# Bluetooth_Module_1R0.net
KiCad netlist of a schematic drawn in Altium Designer
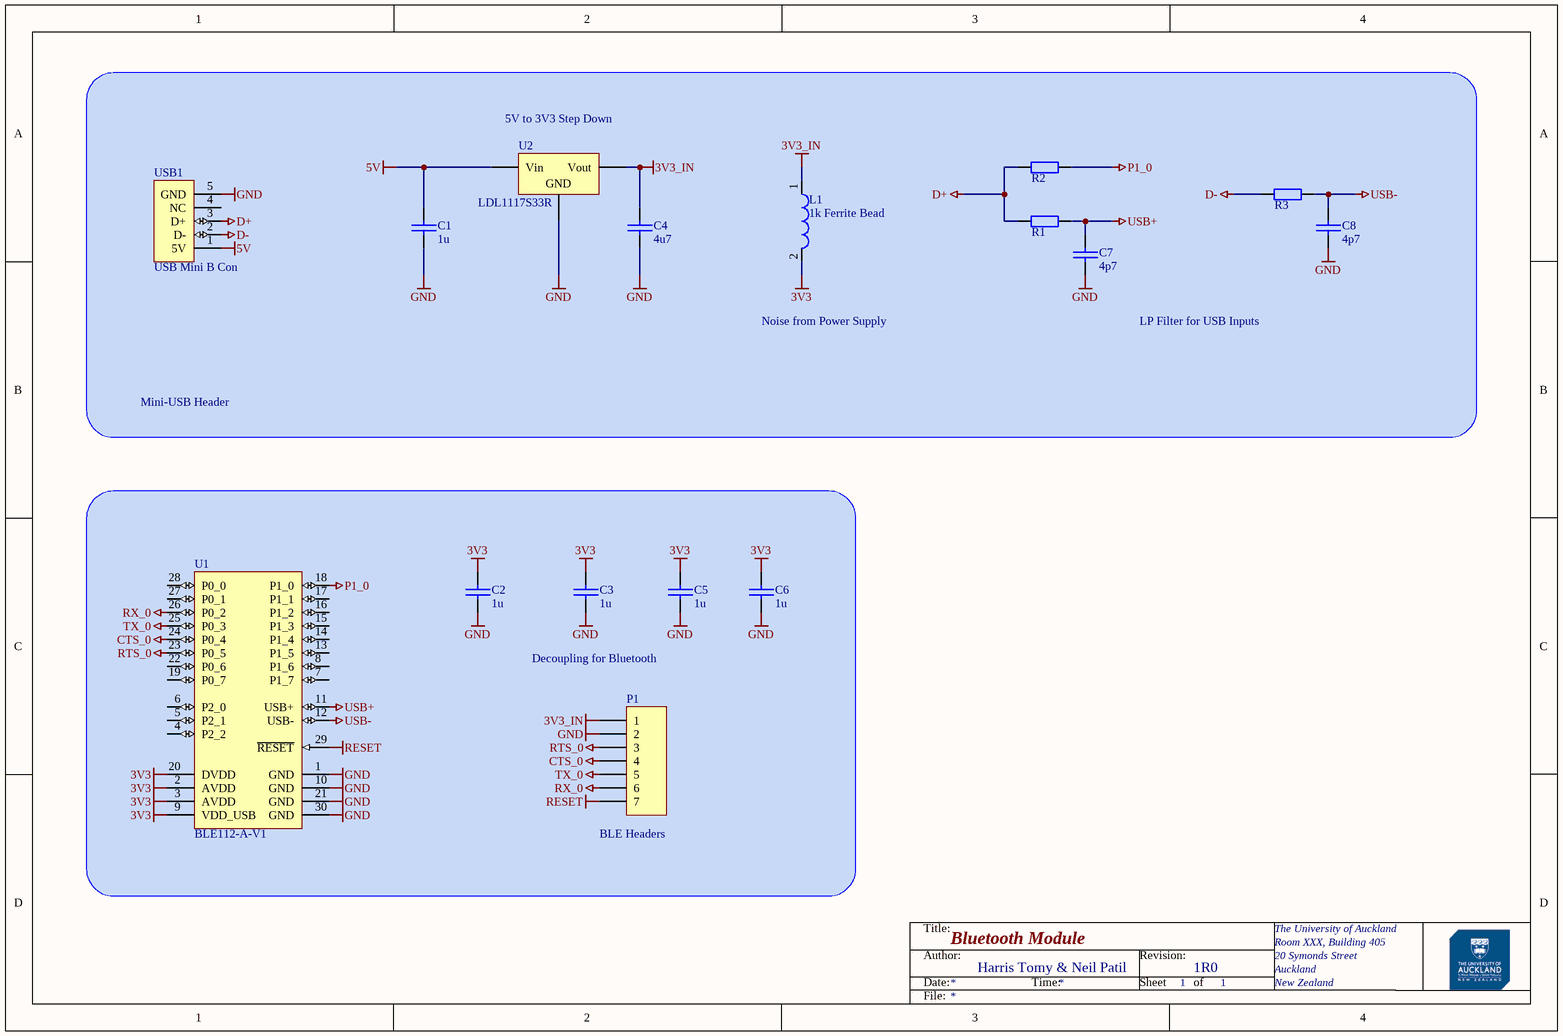
[diagram p0: Bluetooth_Module_1R0.SchDoc]

(export (version "E")
  (design (tool "Eeschema 10.0.6"))
  (components
    (comp (ref "C1")
      (value "1u")
      (footprint "C0805")
      (description "CCAP0805")
      (fields (field (name "MPN") "?"))
      (libsource (lib "E209_Lib") (part "CCAP0805"))
    )
    (comp (ref "C2")
      (value "1u")
      (footprint "C0805")
      (description "CCAP0805")
      (fields (field (name "MPN") "?"))
      (libsource (lib "E209_Lib") (part "CCAP0805"))
    )
    (comp (ref "C3")
      (value "1u")
      (footprint "C0805")
      (description "CCAP0805")
      (fields (field (name "MPN") "?"))
      (libsource (lib "E209_Lib") (part "CCAP0805"))
    )
    (comp (ref "C4")
      (value "4u7")
      (footprint "C1206")
      (description "CAP CER 0.1UF 100V C0G 1206")
      (fields (field (name "MPN") "C3216C0G2A104J160AC") (field (name "MANUFACTURER") "TDK Corporation"))
      (libsource (lib "E209_Lib") (part "Cap CER Decoup C3216C0G2A104J160AC"))
    )
    (comp (ref "C5")
      (value "1u")
      (footprint "C0805")
      (description "CCAP0805")
      (fields (field (name "MPN") "?"))
      (libsource (lib "E209_Lib") (part "CCAP0805"))
    )
    (comp (ref "C6")
      (value "1u")
      (footprint "C0805")
      (description "CCAP0805")
      (fields (field (name "MPN") "?"))
      (libsource (lib "E209_Lib") (part "CCAP0805"))
    )
    (comp (ref "C7")
      (value "4p7")
      (footprint "C0805")
      (description "CCAP0805")
      (fields (field (name "MPN") "?"))
      (libsource (lib "E209_Lib") (part "CCAP0805"))
    )
    (comp (ref "C8")
      (value "4p7")
      (footprint "C0805")
      (description "CCAP0805")
      (fields (field (name "MPN") "?"))
      (libsource (lib "E209_Lib") (part "CCAP0805"))
    )
    (comp (ref "L1")
      (value "1k Ferrite Bead")
      (footprint "SMD-1206")
      (description "SMD EMI Suppression Ferrite Bead WE-CBF, Z = 120 Ohm")
      (fields (field (name "PARTNUMBER") "742792113"))
      (libsource (lib "FE_Bead_1206") (part "742792113"))
    )
    (comp (ref "P1")
      (value "BLE Headers")
      (footprint "HDR1X7")
      (description "Header, 7-Pin")
      (fields (field (name "PUBLISHER") "Altium Limited"))
      (libsource (lib "Miscellaneous Connectors") (part "Header 7"))
    )
    (comp (ref "R1")
      (value "Resistor 0805")
      (footprint "R0805")
      (description "RES0805")
      (fields (field (name "MPN") "?"))
      (libsource (lib "") (part "RES0805_1"))
    )
    (comp (ref "R2")
      (value "Resistor 0805")
      (footprint "R0805")
      (description "RES0805")
      (fields (field (name "MPN") "?"))
      (libsource (lib "E209_Lib") (part "RES0805"))
    )
    (comp (ref "R3")
      (value "Resistor 0805")
      (footprint "R0805")
      (description "RES0805")
      (fields (field (name "MPN") "?"))
      (libsource (lib "") (part "RES0805_1"))
    )
    (comp (ref "U1")
      (value "BLE112-A-V1")
      (footprint "BLUE-BLE112-A-V1_V")
      (libsource (lib "BLE112") (part "BLE112-A-V1"))
    )
    (comp (ref "U2")
      (value "LDL1117S33R")
      (footprint "SOT223L")
      (description "IC REG LINEAR 3.3V 1.2A SOT223")
      (fields (field (name "MANUFACTURER") "STMicroelectronics"))
      (libsource (lib "E209_Lib") (part "LDO LDL1117S33R"))
    )
    (comp (ref "USB1")
      (value "USB Mini B Con")
      (footprint "USB_UJ2MAB")
      (libsource (lib "CommonDevices_V1") (part "USBMiniB"))
    )
  )
  (nets
    (net (code "1") (name "3V3") (class "Default")
      (node (ref "C2") (pin "2") (pinfunction "2_2") (pintype "passive"))
      (node (ref "C3") (pin "2") (pinfunction "2_2") (pintype "passive"))
      (node (ref "C5") (pin "2") (pinfunction "2_2") (pintype "passive"))
      (node (ref "C6") (pin "2") (pinfunction "2_2") (pintype "passive"))
      (node (ref "L1") (pin "2") (pinfunction "2_2") (pintype "passive"))
      (node (ref "U1") (pin "2") (pinfunction "AVDD_2") (pintype "power_in"))
      (node (ref "U1") (pin "20") (pinfunction "DVDD_20") (pintype "power_in"))
      (node (ref "U1") (pin "3") (pinfunction "AVDD_3") (pintype "power_in"))
      (node (ref "U1") (pin "9") (pinfunction "VDD_USB_9") (pintype "power_in"))
    )
    (net (code "2") (name "3V3_IN") (class "Default")
      (node (ref "C4") (pin "2") (pinfunction "2_2") (pintype "passive"))
      (node (ref "L1") (pin "1") (pinfunction "1_1") (pintype "passive"))
      (node (ref "P1") (pin "1") (pinfunction "1_1") (pintype "passive"))
      (node (ref "U2") (pin "2") (pinfunction "Vout_2") (pintype "passive"))
    )
    (net (code "3") (name "5V") (class "Default")
      (node (ref "C1") (pin "2") (pinfunction "2_2") (pintype "passive"))
      (node (ref "U2") (pin "3") (pinfunction "Vin_3") (pintype "passive"))
      (node (ref "USB1") (pin "1") (pinfunction "5V_1") (pintype "passive"))
    )
    (net (code "4") (name "CTS_0") (class "Default")
      (node (ref "P1") (pin "4") (pinfunction "4_4") (pintype "passive"))
      (node (ref "U1") (pin "24") (pinfunction "P0_4_24") (pintype "bidirectional"))
    )
    (net (code "5") (name "D+") (class "Default")
      (node (ref "R1") (pin "2") (pinfunction "2_2") (pintype "passive"))
      (node (ref "R2") (pin "1") (pinfunction "1_1") (pintype "passive"))
      (node (ref "USB1") (pin "3") (pinfunction "D+_3") (pintype "bidirectional"))
    )
    (net (code "6") (name "D-") (class "Default")
      (node (ref "R3") (pin "2") (pinfunction "2_2") (pintype "passive"))
      (node (ref "USB1") (pin "2") (pinfunction "D-_2") (pintype "bidirectional"))
    )
    (net (code "7") (name "GND") (class "Default")
      (node (ref "C1") (pin "1") (pinfunction "1_1") (pintype "passive"))
      (node (ref "C2") (pin "1") (pinfunction "1_1") (pintype "passive"))
      (node (ref "C3") (pin "1") (pinfunction "1_1") (pintype "passive"))
      (node (ref "C4") (pin "1") (pinfunction "1_1") (pintype "passive"))
      (node (ref "C5") (pin "1") (pinfunction "1_1") (pintype "passive"))
      (node (ref "C6") (pin "1") (pinfunction "1_1") (pintype "passive"))
      (node (ref "C7") (pin "1") (pinfunction "1_1") (pintype "passive"))
      (node (ref "C8") (pin "1") (pinfunction "1_1") (pintype "passive"))
      (node (ref "P1") (pin "2") (pinfunction "2_2") (pintype "passive"))
      (node (ref "U1") (pin "1") (pinfunction "GND_1") (pintype "power_in"))
      (node (ref "U1") (pin "10") (pinfunction "GND_10") (pintype "power_in"))
      (node (ref "U1") (pin "21") (pinfunction "GND_21") (pintype "power_in"))
      (node (ref "U1") (pin "30") (pinfunction "GND_30") (pintype "power_in"))
      (node (ref "U2") (pin "1") (pinfunction "GND_1") (pintype "passive"))
      (node (ref "USB1") (pin "5") (pinfunction "GND_5") (pintype "passive"))
    )
    (net (code "8") (name "P1_0") (class "Default")
      (node (ref "R2") (pin "2") (pinfunction "2_2") (pintype "passive"))
      (node (ref "U1") (pin "18") (pinfunction "P1_0_18") (pintype "bidirectional"))
    )
    (net (code "9") (name "RESET") (class "Default")
      (node (ref "P1") (pin "7") (pinfunction "7_7") (pintype "passive"))
      (node (ref "U1") (pin "29") (pinfunction "~{RESET}_29") (pintype "input"))
    )
    (net (code "10") (name "RTS_0") (class "Default")
      (node (ref "P1") (pin "3") (pinfunction "3_3") (pintype "passive"))
      (node (ref "U1") (pin "23") (pinfunction "P0_5_23") (pintype "bidirectional"))
    )
    (net (code "11") (name "RX_0") (class "Default")
      (node (ref "P1") (pin "6") (pinfunction "6_6") (pintype "passive"))
      (node (ref "U1") (pin "26") (pinfunction "P0_2_26") (pintype "bidirectional"))
    )
    (net (code "12") (name "TX_0") (class "Default")
      (node (ref "P1") (pin "5") (pinfunction "5_5") (pintype "passive"))
      (node (ref "U1") (pin "25") (pinfunction "P0_3_25") (pintype "bidirectional"))
    )
    (net (code "13") (name "USB+") (class "Default")
      (node (ref "C7") (pin "2") (pinfunction "2_2") (pintype "passive"))
      (node (ref "R1") (pin "1") (pinfunction "1_1") (pintype "passive"))
      (node (ref "U1") (pin "11") (pinfunction "USB+_11") (pintype "bidirectional"))
    )
    (net (code "14") (name "USB-") (class "Default")
      (node (ref "C8") (pin "2") (pinfunction "2_2") (pintype "passive"))
      (node (ref "R3") (pin "1") (pinfunction "1_1") (pintype "passive"))
      (node (ref "U1") (pin "12") (pinfunction "USB-_12") (pintype "bidirectional"))
    )
    (net (code "15") (name "unconnected-(U1-P0_0-Pad28)") (class "Default")
      (node (ref "U1") (pin "28") (pinfunction "P0_0_28") (pintype "bidirectional"))
    )
    (net (code "16") (name "unconnected-(U1-P0_1-Pad27)") (class "Default")
      (node (ref "U1") (pin "27") (pinfunction "P0_1_27") (pintype "bidirectional"))
    )
    (net (code "17") (name "unconnected-(U1-P0_6-Pad22)") (class "Default")
      (node (ref "U1") (pin "22") (pinfunction "P0_6_22") (pintype "bidirectional"))
    )
    (net (code "18") (name "unconnected-(U1-P0_7-Pad19)") (class "Default")
      (node (ref "U1") (pin "19") (pinfunction "P0_7_19") (pintype "bidirectional"))
    )
    (net (code "19") (name "unconnected-(U1-P1_1-Pad17)") (class "Default")
      (node (ref "U1") (pin "17") (pinfunction "P1_1_17") (pintype "bidirectional"))
    )
    (net (code "20") (name "unconnected-(U1-P1_2-Pad16)") (class "Default")
      (node (ref "U1") (pin "16") (pinfunction "P1_2_16") (pintype "bidirectional"))
    )
    (net (code "21") (name "unconnected-(U1-P1_3-Pad15)") (class "Default")
      (node (ref "U1") (pin "15") (pinfunction "P1_3_15") (pintype "bidirectional"))
    )
    (net (code "22") (name "unconnected-(U1-P1_4-Pad14)") (class "Default")
      (node (ref "U1") (pin "14") (pinfunction "P1_4_14") (pintype "bidirectional"))
    )
    (net (code "23") (name "unconnected-(U1-P1_5-Pad13)") (class "Default")
      (node (ref "U1") (pin "13") (pinfunction "P1_5_13") (pintype "bidirectional"))
    )
    (net (code "24") (name "unconnected-(U1-P1_6-Pad8)") (class "Default")
      (node (ref "U1") (pin "8") (pinfunction "P1_6_8") (pintype "bidirectional"))
    )
    (net (code "25") (name "unconnected-(U1-P1_7-Pad7)") (class "Default")
      (node (ref "U1") (pin "7") (pinfunction "P1_7_7") (pintype "bidirectional"))
    )
    (net (code "26") (name "unconnected-(U1-P2_0-Pad6)") (class "Default")
      (node (ref "U1") (pin "6") (pinfunction "P2_0_6") (pintype "bidirectional"))
    )
    (net (code "27") (name "unconnected-(U1-P2_1-Pad5)") (class "Default")
      (node (ref "U1") (pin "5") (pinfunction "P2_1_5") (pintype "bidirectional"))
    )
    (net (code "28") (name "unconnected-(U1-P2_2-Pad4)") (class "Default")
      (node (ref "U1") (pin "4") (pinfunction "P2_2_4") (pintype "bidirectional"))
    )
    (net (code "29") (name "unconnected-(USB1-NC-Pad4)") (class "Default")
      (node (ref "USB1") (pin "4") (pinfunction "NC_4") (pintype "passive"))
    )
  )
)
